# rPiMotors_v1_2.net
KiCad netlist of a schematic drawn in EAGLE
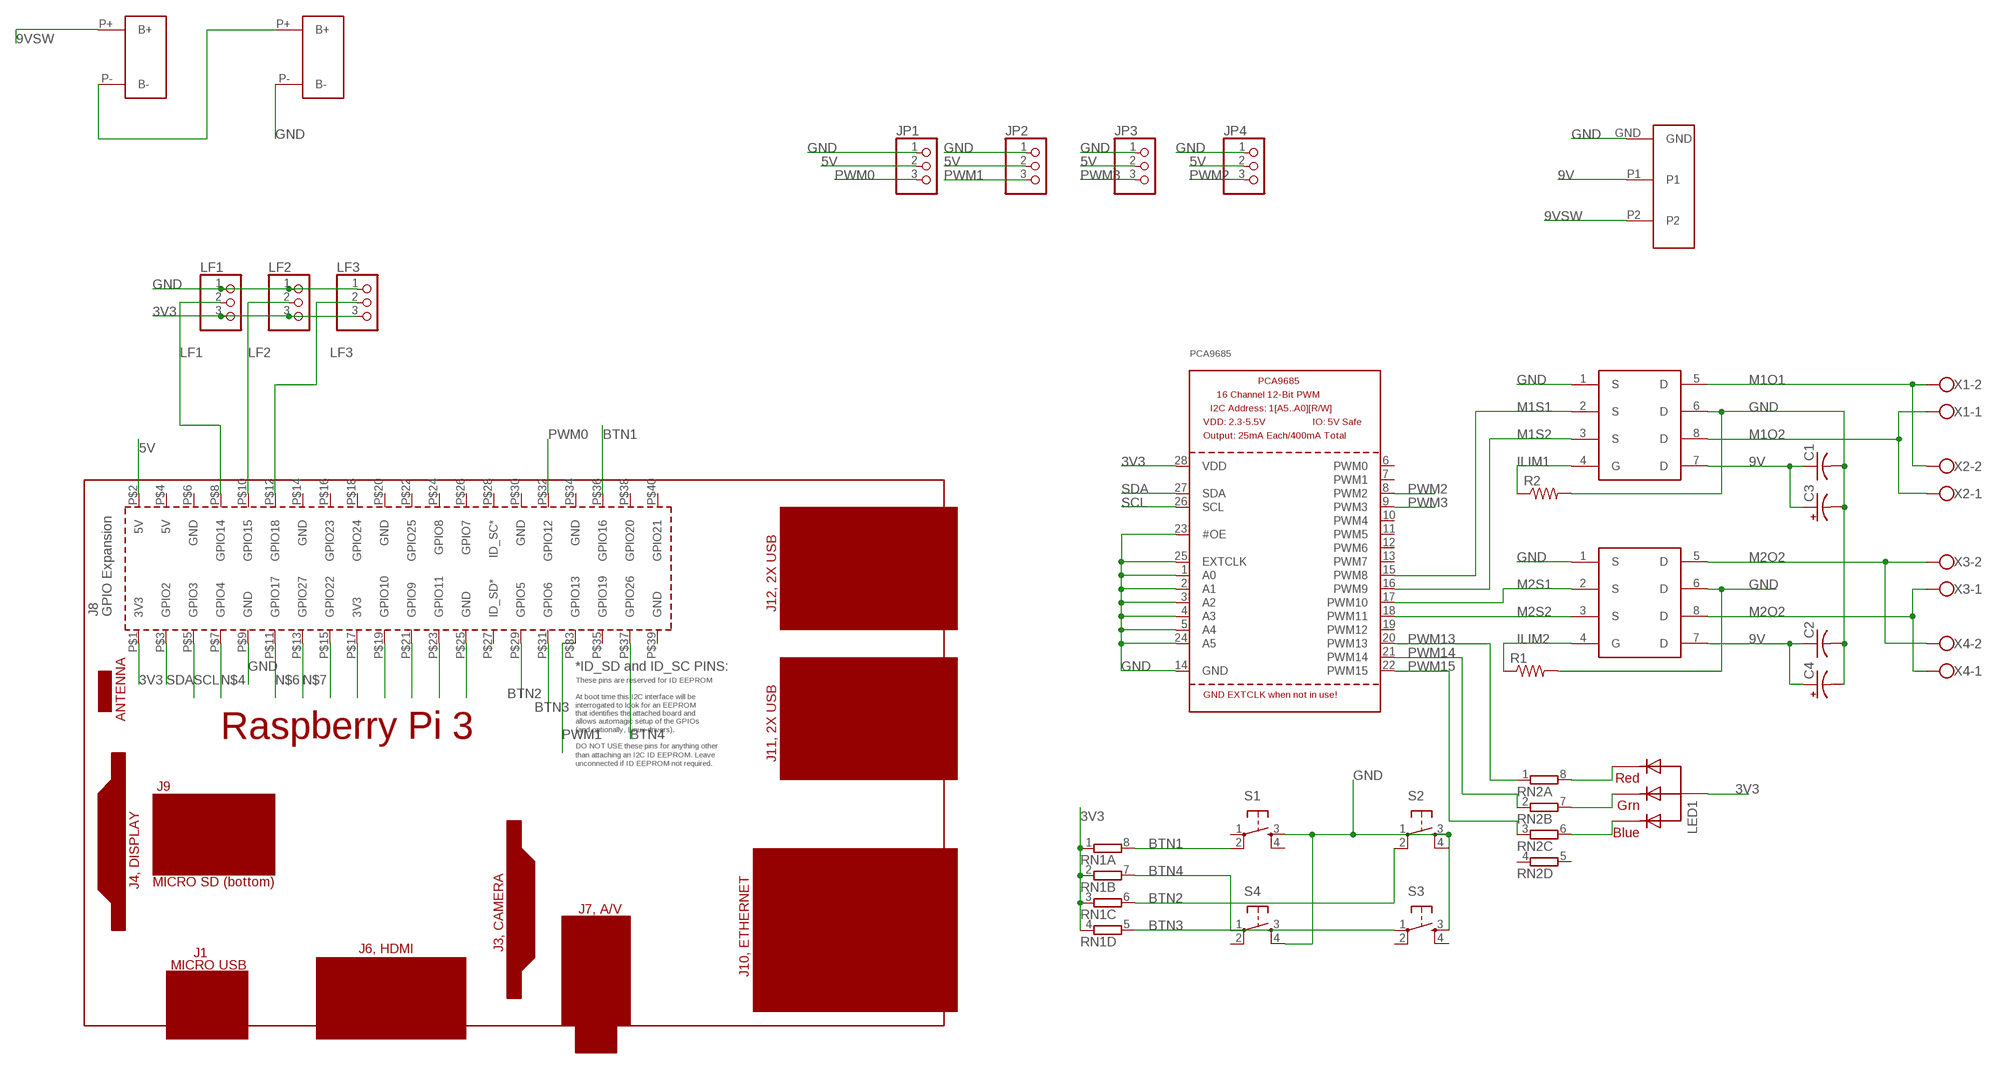
[diagram p0: schematic, sheet 1]

(export (version "E")
  (design (tool "Eeschema 10.0.6"))
  (components
    (comp (ref "C1")
      (value "C-USC0603")
      (footprint "eagle-import:C0603")
      (libsource (lib "eagle-import") (part "C-USC0603"))
    )
    (comp (ref "C2")
      (value "C-USC0603")
      (footprint "eagle-import:C0603")
      (libsource (lib "eagle-import") (part "C-USC0603"))
    )
    (comp (ref "C3")
      (value "CPOL-USD")
      (footprint "eagle-import:PANASONIC_D")
      (libsource (lib "eagle-import") (part "CPOL-USD"))
    )
    (comp (ref "C4")
      (value "CPOL-USD")
      (footprint "eagle-import:PANASONIC_D")
      (libsource (lib "eagle-import") (part "CPOL-USD"))
    )
    (comp (ref "JP1")
      (value "PINHD-1X3")
      (footprint "eagle-import:1X03")
      (libsource (lib "eagle-import") (part "PINHD-1X3"))
    )
    (comp (ref "JP2")
      (value "PINHD-1X3")
      (footprint "eagle-import:1X03")
      (libsource (lib "eagle-import") (part "PINHD-1X3"))
    )
    (comp (ref "JP3")
      (value "PINHD-1X3")
      (footprint "eagle-import:1X03")
      (libsource (lib "eagle-import") (part "PINHD-1X3"))
    )
    (comp (ref "JP4")
      (value "PINHD-1X3")
      (footprint "eagle-import:1X03")
      (libsource (lib "eagle-import") (part "PINHD-1X3"))
    )
    (comp (ref "LED1")
      (value "RGBLED_CA")
      (footprint "eagle-import:5MMRGB")
      (libsource (lib "eagle-import") (part "RGBLED_CA"))
    )
    (comp (ref "LF1")
      (value "PINHD-1X3")
      (footprint "eagle-import:1X03")
      (libsource (lib "eagle-import") (part "PINHD-1X3"))
    )
    (comp (ref "LF2")
      (value "PINHD-1X3")
      (footprint "eagle-import:1X03")
      (libsource (lib "eagle-import") (part "PINHD-1X3"))
    )
    (comp (ref "LF3")
      (value "PINHD-1X3")
      (footprint "eagle-import:1X03")
      (libsource (lib "eagle-import") (part "PINHD-1X3"))
    )
    (comp (ref "PCA9685")
      (value "PCA9685")
      (footprint "eagle-import:TSSOP28")
      (libsource (lib "eagle-import") (part "PCA9685"))
    )
    (comp (ref "PCB1")
      (value "RPI3")
      (footprint "eagle-import:RPI3")
      (libsource (lib "eagle-import") (part "RPI3"))
    )
    (comp (ref "R1")
      (value "R-US_R0603")
      (footprint "eagle-import:R0603")
      (libsource (lib "eagle-import") (part "R-US_R0603"))
    )
    (comp (ref "R2")
      (value "R-US_R0603")
      (footprint "eagle-import:R0603")
      (libsource (lib "eagle-import") (part "R-US_R0603"))
    )
    (comp (ref "RN1")
      (value "4R-N0603-ARV")
      (footprint "eagle-import:0603-ARV")
      (libsource (lib "eagle-import") (part "4R-N0603-ARV"))
    )
    (comp (ref "RN2")
      (value "4R-N0603-ARV")
      (footprint "eagle-import:0603-ARV")
      (libsource (lib "eagle-import") (part "4R-N0603-ARV"))
    )
    (comp (ref "S1")
      (value "TAC_SWITCHPTH")
      (footprint "eagle-import:TACTILE-PTH")
      (libsource (lib "eagle-import") (part "TAC_SWITCHPTH"))
    )
    (comp (ref "S2")
      (value "TAC_SWITCHPTH")
      (footprint "eagle-import:TACTILE-PTH")
      (libsource (lib "eagle-import") (part "TAC_SWITCHPTH"))
    )
    (comp (ref "S3")
      (value "TAC_SWITCHPTH")
      (footprint "eagle-import:TACTILE-PTH")
      (libsource (lib "eagle-import") (part "TAC_SWITCHPTH"))
    )
    (comp (ref "S4")
      (value "TAC_SWITCHPTH")
      (footprint "eagle-import:TACTILE-PTH")
      (libsource (lib "eagle-import") (part "TAC_SWITCHPTH"))
    )
    (comp (ref "U$1")
      (value "NDS8434")
      (footprint "eagle-import:SO08")
      (libsource (lib "eagle-import") (part "NDS8434"))
    )
    (comp (ref "U$2")
      (value "NDS8434")
      (footprint "eagle-import:SO08")
      (libsource (lib "eagle-import") (part "NDS8434"))
    )
    (comp (ref "U$3")
      (value "ROCKER")
      (footprint "eagle-import:ROCKER")
      (libsource (lib "eagle-import") (part "ROCKER"))
    )
    (comp (ref "U$4")
      (value "BATTERY")
      (footprint "eagle-import:BATTERY")
      (libsource (lib "eagle-import") (part "BATTERY"))
    )
    (comp (ref "U$5")
      (value "BATTERY")
      (footprint "eagle-import:BATTERY")
      (libsource (lib "eagle-import") (part "BATTERY"))
    )
    (comp (ref "X1")
      (value "SCREWCONNECTOR")
      (footprint "eagle-import:2PIN-SCREW-TERMINAL")
      (fields (field (name "MPN") "237-102"))
      (libsource (lib "eagle-import") (part "SCREWCONNECTOR"))
    )
    (comp (ref "X2")
      (value "SCREWCONNECTOR")
      (footprint "eagle-import:2PIN-SCREW-TERMINAL")
      (fields (field (name "MPN") "237-102"))
      (libsource (lib "eagle-import") (part "SCREWCONNECTOR"))
    )
    (comp (ref "X3")
      (value "SCREWCONNECTOR")
      (footprint "eagle-import:2PIN-SCREW-TERMINAL")
      (fields (field (name "MPN") "237-102"))
      (libsource (lib "eagle-import") (part "SCREWCONNECTOR"))
    )
    (comp (ref "X4")
      (value "SCREWCONNECTOR")
      (footprint "eagle-import:2PIN-SCREW-TERMINAL")
      (fields (field (name "MPN") "237-102"))
      (libsource (lib "eagle-import") (part "SCREWCONNECTOR"))
    )
  )
  (nets
    (net (code "1") (name "/3V3") (class "Default")
      (node (ref "LED1") (pin "2") (pinfunction "VCC_2") (pintype "bidirectional"))
      (node (ref "LF1") (pin "3") (pinfunction "3_3") (pintype "passive"))
      (node (ref "LF2") (pin "3") (pinfunction "3_3") (pintype "passive"))
      (node (ref "LF3") (pin "3") (pinfunction "3_3") (pintype "passive"))
      (node (ref "PCA9685") (pin "28") (pinfunction "VDD_28") (pintype "power_in"))
      (node (ref "PCB1") (pin "P$1") (pinfunction "3V3_P$1") (pintype "bidirectional"))
      (node (ref "RN1") (pin "1") (pinfunction "1_1") (pintype "passive"))
      (node (ref "RN1") (pin "2") (pinfunction "1_2") (pintype "passive"))
      (node (ref "RN1") (pin "3") (pinfunction "1_3") (pintype "passive"))
      (node (ref "RN1") (pin "4") (pinfunction "1_4") (pintype "passive"))
    )
    (net (code "2") (name "/5V") (class "Default")
      (node (ref "JP1") (pin "2") (pinfunction "2_2") (pintype "passive"))
      (node (ref "JP2") (pin "2") (pinfunction "2_2") (pintype "passive"))
      (node (ref "JP3") (pin "2") (pinfunction "2_2") (pintype "passive"))
      (node (ref "JP4") (pin "2") (pinfunction "2_2") (pintype "passive"))
      (node (ref "PCB1") (pin "P$2") (pinfunction "5V_P$2") (pintype "bidirectional"))
    )
    (net (code "3") (name "/9V") (class "Default")
      (node (ref "C1") (pin "1") (pinfunction "1_1") (pintype "passive"))
      (node (ref "C2") (pin "1") (pinfunction "1_1") (pintype "passive"))
      (node (ref "C3") (pin "+") (pinfunction "+_+") (pintype "passive"))
      (node (ref "C4") (pin "+") (pinfunction "+_+") (pintype "passive"))
      (node (ref "U$1") (pin "7") (pinfunction "D_7") (pintype "bidirectional"))
      (node (ref "U$2") (pin "7") (pinfunction "D_7") (pintype "bidirectional"))
      (node (ref "U$3") (pin "P1") (pinfunction "P1_P1") (pintype "bidirectional"))
    )
    (net (code "4") (name "/9VSW") (class "Default")
      (node (ref "U$3") (pin "P2") (pinfunction "P2_P2") (pintype "bidirectional"))
      (node (ref "U$4") (pin "P+") (pinfunction "B+_P+") (pintype "bidirectional"))
    )
    (net (code "5") (name "/BTN1") (class "Default")
      (node (ref "PCB1") (pin "P$36") (pinfunction "GPIO16_P$36") (pintype "bidirectional"))
      (node (ref "RN1") (pin "8") (pinfunction "2_8") (pintype "passive"))
      (node (ref "S1") (pin "2") (pinfunction "2_2") (pintype "passive"))
    )
    (net (code "6") (name "/BTN2") (class "Default")
      (node (ref "PCB1") (pin "P$29") (pinfunction "GPIO5_P$29") (pintype "bidirectional"))
      (node (ref "RN1") (pin "6") (pinfunction "2_6") (pintype "passive"))
      (node (ref "S2") (pin "2") (pinfunction "2_2") (pintype "passive"))
    )
    (net (code "7") (name "/BTN3") (class "Default")
      (node (ref "PCB1") (pin "P$31") (pinfunction "GPIO6_P$31") (pintype "bidirectional"))
      (node (ref "RN1") (pin "5") (pinfunction "2_5") (pintype "passive"))
      (node (ref "S3") (pin "1") (pinfunction "1_1") (pintype "passive"))
    )
    (net (code "8") (name "/BTN4") (class "Default")
      (node (ref "PCB1") (pin "P$37") (pinfunction "GPIO26_P$37") (pintype "bidirectional"))
      (node (ref "RN1") (pin "7") (pinfunction "2_7") (pintype "passive"))
      (node (ref "S4") (pin "1") (pinfunction "1_1") (pintype "passive"))
    )
    (net (code "9") (name "/GND") (class "Default")
      (node (ref "C1") (pin "2") (pinfunction "2_2") (pintype "passive"))
      (node (ref "C2") (pin "2") (pinfunction "2_2") (pintype "passive"))
      (node (ref "C3") (pin "-") (pinfunction "-_-") (pintype "passive"))
      (node (ref "C4") (pin "-") (pinfunction "-_-") (pintype "passive"))
      (node (ref "JP1") (pin "1") (pinfunction "1_1") (pintype "passive"))
      (node (ref "JP2") (pin "1") (pinfunction "1_1") (pintype "passive"))
      (node (ref "JP3") (pin "1") (pinfunction "1_1") (pintype "passive"))
      (node (ref "JP4") (pin "1") (pinfunction "1_1") (pintype "passive"))
      (node (ref "LF1") (pin "1") (pinfunction "1_1") (pintype "passive"))
      (node (ref "LF2") (pin "1") (pinfunction "1_1") (pintype "passive"))
      (node (ref "LF3") (pin "1") (pinfunction "1_1") (pintype "passive"))
      (node (ref "PCA9685") (pin "1") (pinfunction "A0_1") (pintype "bidirectional"))
      (node (ref "PCA9685") (pin "14") (pinfunction "GND_14") (pintype "power_in"))
      (node (ref "PCA9685") (pin "2") (pinfunction "A1_2") (pintype "bidirectional"))
      (node (ref "PCA9685") (pin "23") (pinfunction "#OE_23") (pintype "input"))
      (node (ref "PCA9685") (pin "24") (pinfunction "A5_24") (pintype "bidirectional"))
      (node (ref "PCA9685") (pin "25") (pinfunction "EXTCLK_25") (pintype "input"))
      (node (ref "PCA9685") (pin "3") (pinfunction "A2_3") (pintype "bidirectional"))
      (node (ref "PCA9685") (pin "4") (pinfunction "A3_4") (pintype "bidirectional"))
      (node (ref "PCA9685") (pin "5") (pinfunction "A4_5") (pintype "bidirectional"))
      (node (ref "PCB1") (pin "P$9") (pinfunction "GND_P$9") (pintype "bidirectional"))
      (node (ref "R1") (pin "2") (pinfunction "2_2") (pintype "passive"))
      (node (ref "R2") (pin "2") (pinfunction "2_2") (pintype "passive"))
      (node (ref "S1") (pin "3") (pinfunction "3_3") (pintype "passive"))
      (node (ref "S2") (pin "3") (pinfunction "3_3") (pintype "passive"))
      (node (ref "S3") (pin "3") (pinfunction "3_3") (pintype "passive"))
      (node (ref "S4") (pin "4") (pinfunction "4_4") (pintype "passive"))
      (node (ref "U$1") (pin "1") (pinfunction "S_1") (pintype "bidirectional"))
      (node (ref "U$1") (pin "6") (pinfunction "D_6") (pintype "bidirectional"))
      (node (ref "U$2") (pin "1") (pinfunction "S_1") (pintype "bidirectional"))
      (node (ref "U$2") (pin "6") (pinfunction "D_6") (pintype "bidirectional"))
      (node (ref "U$3") (pin "GND") (pinfunction "GND_GND") (pintype "bidirectional"))
      (node (ref "U$5") (pin "P-") (pinfunction "B-_P-") (pintype "bidirectional"))
    )
    (net (code "10") (name "/ILIM1") (class "Default")
      (node (ref "R2") (pin "1") (pinfunction "1_1") (pintype "passive"))
      (node (ref "U$1") (pin "4") (pinfunction "G_4") (pintype "bidirectional"))
    )
    (net (code "11") (name "/ILIM2") (class "Default")
      (node (ref "R1") (pin "1") (pinfunction "1_1") (pintype "passive"))
      (node (ref "U$2") (pin "4") (pinfunction "G_4") (pintype "bidirectional"))
    )
    (net (code "12") (name "/LF1") (class "Default")
      (node (ref "LF1") (pin "2") (pinfunction "2_2") (pintype "passive"))
      (node (ref "PCB1") (pin "P$8") (pinfunction "GPIO14_P$8") (pintype "bidirectional"))
    )
    (net (code "13") (name "/LF2") (class "Default")
      (node (ref "LF2") (pin "2") (pinfunction "2_2") (pintype "passive"))
      (node (ref "PCB1") (pin "P$10") (pinfunction "GPIO15_P$10") (pintype "bidirectional"))
    )
    (net (code "14") (name "/LF3") (class "Default")
      (node (ref "LF3") (pin "2") (pinfunction "2_2") (pintype "passive"))
      (node (ref "PCB1") (pin "P$12") (pinfunction "GPIO18_P$12") (pintype "bidirectional"))
    )
    (net (code "15") (name "/M1O1") (class "Default")
      (node (ref "U$1") (pin "5") (pinfunction "D_5") (pintype "bidirectional"))
      (node (ref "X1") (pin "2") (pinfunction "KL_2") (pintype "passive"))
      (node (ref "X2") (pin "2") (pinfunction "KL_2") (pintype "passive"))
    )
    (net (code "16") (name "/M1O2") (class "Default")
      (node (ref "U$1") (pin "8") (pinfunction "D_8") (pintype "bidirectional"))
      (node (ref "X1") (pin "1") (pinfunction "KL_1") (pintype "passive"))
      (node (ref "X2") (pin "1") (pinfunction "KL_1") (pintype "passive"))
    )
    (net (code "17") (name "/M1S1") (class "Default")
      (node (ref "PCA9685") (pin "15") (pinfunction "PWM8_15") (pintype "output"))
      (node (ref "U$1") (pin "2") (pinfunction "S_2") (pintype "bidirectional"))
    )
    (net (code "18") (name "/M1S2") (class "Default")
      (node (ref "PCA9685") (pin "16") (pinfunction "PWM9_16") (pintype "output"))
      (node (ref "U$1") (pin "3") (pinfunction "S_3") (pintype "bidirectional"))
    )
    (net (code "19") (name "/M2O2") (class "Default")
      (node (ref "U$2") (pin "5") (pinfunction "D_5") (pintype "bidirectional"))
      (node (ref "U$2") (pin "8") (pinfunction "D_8") (pintype "bidirectional"))
      (node (ref "X3") (pin "1") (pinfunction "KL_1") (pintype "passive"))
      (node (ref "X3") (pin "2") (pinfunction "KL_2") (pintype "passive"))
      (node (ref "X4") (pin "1") (pinfunction "KL_1") (pintype "passive"))
      (node (ref "X4") (pin "2") (pinfunction "KL_2") (pintype "passive"))
    )
    (net (code "20") (name "/M2S1") (class "Default")
      (node (ref "PCA9685") (pin "17") (pinfunction "PWM10_17") (pintype "output"))
      (node (ref "U$2") (pin "2") (pinfunction "S_2") (pintype "bidirectional"))
    )
    (net (code "21") (name "/M2S2") (class "Default")
      (node (ref "PCA9685") (pin "18") (pinfunction "PWM11_18") (pintype "output"))
      (node (ref "U$2") (pin "3") (pinfunction "S_3") (pintype "bidirectional"))
    )
    (net (code "22") (name "/N$4") (class "Default")
      (node (ref "PCB1") (pin "P$7") (pinfunction "GPIO4_P$7") (pintype "bidirectional"))
    )
    (net (code "23") (name "/N$6") (class "Default")
      (node (ref "PCB1") (pin "P$11") (pinfunction "GPIO17_P$11") (pintype "bidirectional"))
    )
    (net (code "24") (name "/N$7") (class "Default")
      (node (ref "PCB1") (pin "P$13") (pinfunction "GPIO27_P$13") (pintype "bidirectional"))
    )
    (net (code "25") (name "/PWM0") (class "Default")
      (node (ref "JP1") (pin "3") (pinfunction "3_3") (pintype "passive"))
      (node (ref "PCB1") (pin "P$32") (pinfunction "GPIO12_P$32") (pintype "bidirectional"))
    )
    (net (code "26") (name "/PWM1") (class "Default")
      (node (ref "JP2") (pin "3") (pinfunction "3_3") (pintype "passive"))
      (node (ref "PCB1") (pin "P$33") (pinfunction "GPIO13_P$33") (pintype "bidirectional"))
    )
    (net (code "27") (name "/PWM2") (class "Default")
      (node (ref "JP4") (pin "3") (pinfunction "3_3") (pintype "passive"))
      (node (ref "PCA9685") (pin "8") (pinfunction "PWM2_8") (pintype "output"))
    )
    (net (code "28") (name "/PWM3") (class "Default")
      (node (ref "JP3") (pin "3") (pinfunction "3_3") (pintype "passive"))
      (node (ref "PCA9685") (pin "9") (pinfunction "PWM3_9") (pintype "output"))
    )
    (net (code "29") (name "/PWM13") (class "Default")
      (node (ref "PCA9685") (pin "20") (pinfunction "PWM13_20") (pintype "output"))
      (node (ref "RN2") (pin "1") (pinfunction "1_1") (pintype "passive"))
    )
    (net (code "30") (name "/PWM14") (class "Default")
      (node (ref "PCA9685") (pin "21") (pinfunction "PWM14_21") (pintype "output"))
      (node (ref "RN2") (pin "2") (pinfunction "1_2") (pintype "passive"))
    )
    (net (code "31") (name "/PWM15") (class "Default")
      (node (ref "PCA9685") (pin "22") (pinfunction "PWM15_22") (pintype "output"))
      (node (ref "RN2") (pin "3") (pinfunction "1_3") (pintype "passive"))
    )
    (net (code "32") (name "/SCL") (class "Default")
      (node (ref "PCA9685") (pin "26") (pinfunction "SCL_26") (pintype "bidirectional"))
      (node (ref "PCB1") (pin "P$5") (pinfunction "GPIO3_P$5") (pintype "bidirectional"))
    )
    (net (code "33") (name "/SDA") (class "Default")
      (node (ref "PCA9685") (pin "27") (pinfunction "SDA_27") (pintype "bidirectional"))
      (node (ref "PCB1") (pin "P$3") (pinfunction "GPIO2_P$3") (pintype "bidirectional"))
    )
    (net (code "34") (name "Net-(LED1-BLUE)") (class "Default")
      (node (ref "LED1") (pin "1") (pinfunction "BLUE_1") (pintype "bidirectional"))
      (node (ref "RN2") (pin "6") (pinfunction "2_6") (pintype "passive"))
    )
    (net (code "35") (name "Net-(LED1-GREEN)") (class "Default")
      (node (ref "LED1") (pin "3") (pinfunction "GREEN_3") (pintype "bidirectional"))
      (node (ref "RN2") (pin "7") (pinfunction "2_7") (pintype "passive"))
    )
    (net (code "36") (name "Net-(LED1-RED)") (class "Default")
      (node (ref "LED1") (pin "4") (pinfunction "RED_4") (pintype "bidirectional"))
      (node (ref "RN2") (pin "8") (pinfunction "2_8") (pintype "passive"))
    )
    (net (code "37") (name "Net-(U$4-B-)") (class "Default")
      (node (ref "U$4") (pin "P-") (pinfunction "B-_P-") (pintype "bidirectional"))
      (node (ref "U$5") (pin "P+") (pinfunction "B+_P+") (pintype "bidirectional"))
    )
    (net (code "38") (name "unconnected-(PCA9685-PWM0-Pad6)") (class "Default")
      (node (ref "PCA9685") (pin "6") (pinfunction "PWM0_6") (pintype "output"))
    )
    (net (code "39") (name "unconnected-(PCA9685-PWM1-Pad7)") (class "Default")
      (node (ref "PCA9685") (pin "7") (pinfunction "PWM1_7") (pintype "output"))
    )
    (net (code "40") (name "unconnected-(PCA9685-PWM4-Pad10)") (class "Default")
      (node (ref "PCA9685") (pin "10") (pinfunction "PWM4_10") (pintype "output"))
    )
    (net (code "41") (name "unconnected-(PCA9685-PWM5-Pad11)") (class "Default")
      (node (ref "PCA9685") (pin "11") (pinfunction "PWM5_11") (pintype "output"))
    )
    (net (code "42") (name "unconnected-(PCA9685-PWM6-Pad12)") (class "Default")
      (node (ref "PCA9685") (pin "12") (pinfunction "PWM6_12") (pintype "output"))
    )
    (net (code "43") (name "unconnected-(PCA9685-PWM7-Pad13)") (class "Default")
      (node (ref "PCA9685") (pin "13") (pinfunction "PWM7_13") (pintype "output"))
    )
    (net (code "44") (name "unconnected-(PCA9685-PWM12-Pad19)") (class "Default")
      (node (ref "PCA9685") (pin "19") (pinfunction "PWM12_19") (pintype "output"))
    )
    (net (code "45") (name "unconnected-(PCB1-3V3-PadP$17)") (class "Default")
      (node (ref "PCB1") (pin "P$17") (pinfunction "3V3_P$17") (pintype "bidirectional"))
    )
    (net (code "46") (name "unconnected-(PCB1-5V-PadP$4)") (class "Default")
      (node (ref "PCB1") (pin "P$4") (pinfunction "5V_P$4") (pintype "bidirectional"))
    )
    (net (code "47") (name "unconnected-(PCB1-GND-PadP$6)") (class "Default")
      (node (ref "PCB1") (pin "P$6") (pinfunction "GND_P$6") (pintype "bidirectional"))
    )
    (net (code "48") (name "unconnected-(PCB1-GND-PadP$14)") (class "Default")
      (node (ref "PCB1") (pin "P$14") (pinfunction "GND_P$14") (pintype "bidirectional"))
    )
    (net (code "49") (name "unconnected-(PCB1-GND-PadP$20)") (class "Default")
      (node (ref "PCB1") (pin "P$20") (pinfunction "GND_P$20") (pintype "bidirectional"))
    )
    (net (code "50") (name "unconnected-(PCB1-GND-PadP$25)") (class "Default")
      (node (ref "PCB1") (pin "P$25") (pinfunction "GND_P$25") (pintype "bidirectional"))
    )
    (net (code "51") (name "unconnected-(PCB1-GND-PadP$30)") (class "Default")
      (node (ref "PCB1") (pin "P$30") (pinfunction "GND_P$30") (pintype "bidirectional"))
    )
    (net (code "52") (name "unconnected-(PCB1-GND-PadP$34)") (class "Default")
      (node (ref "PCB1") (pin "P$34") (pinfunction "GND_P$34") (pintype "bidirectional"))
    )
    (net (code "53") (name "unconnected-(PCB1-GND-PadP$39)") (class "Default")
      (node (ref "PCB1") (pin "P$39") (pinfunction "GND_P$39") (pintype "bidirectional"))
    )
    (net (code "54") (name "unconnected-(PCB1-GPIO7-PadP$26)") (class "Default")
      (node (ref "PCB1") (pin "P$26") (pinfunction "GPIO7_P$26") (pintype "bidirectional"))
    )
    (net (code "55") (name "unconnected-(PCB1-GPIO8-PadP$24)") (class "Default")
      (node (ref "PCB1") (pin "P$24") (pinfunction "GPIO8_P$24") (pintype "bidirectional"))
    )
    (net (code "56") (name "unconnected-(PCB1-GPIO9-PadP$21)") (class "Default")
      (node (ref "PCB1") (pin "P$21") (pinfunction "GPIO9_P$21") (pintype "bidirectional"))
    )
    (net (code "57") (name "unconnected-(PCB1-GPIO10-PadP$19)") (class "Default")
      (node (ref "PCB1") (pin "P$19") (pinfunction "GPIO10_P$19") (pintype "bidirectional"))
    )
    (net (code "58") (name "unconnected-(PCB1-GPIO11-PadP$23)") (class "Default")
      (node (ref "PCB1") (pin "P$23") (pinfunction "GPIO11_P$23") (pintype "bidirectional"))
    )
    (net (code "59") (name "unconnected-(PCB1-GPIO19-PadP$35)") (class "Default")
      (node (ref "PCB1") (pin "P$35") (pinfunction "GPIO19_P$35") (pintype "bidirectional"))
    )
    (net (code "60") (name "unconnected-(PCB1-GPIO20-PadP$38)") (class "Default")
      (node (ref "PCB1") (pin "P$38") (pinfunction "GPIO20_P$38") (pintype "bidirectional"))
    )
    (net (code "61") (name "unconnected-(PCB1-GPIO21-PadP$40)") (class "Default")
      (node (ref "PCB1") (pin "P$40") (pinfunction "GPIO21_P$40") (pintype "bidirectional"))
    )
    (net (code "62") (name "unconnected-(PCB1-GPIO22-PadP$15)") (class "Default")
      (node (ref "PCB1") (pin "P$15") (pinfunction "GPIO22_P$15") (pintype "bidirectional"))
    )
    (net (code "63") (name "unconnected-(PCB1-GPIO23-PadP$16)") (class "Default")
      (node (ref "PCB1") (pin "P$16") (pinfunction "GPIO23_P$16") (pintype "bidirectional"))
    )
    (net (code "64") (name "unconnected-(PCB1-GPIO24-PadP$18)") (class "Default")
      (node (ref "PCB1") (pin "P$18") (pinfunction "GPIO24_P$18") (pintype "bidirectional"))
    )
    (net (code "65") (name "unconnected-(PCB1-GPIO25-PadP$22)") (class "Default")
      (node (ref "PCB1") (pin "P$22") (pinfunction "GPIO25_P$22") (pintype "bidirectional"))
    )
    (net (code "66") (name "unconnected-(PCB1-ID_SC*-PadP$28)") (class "Default")
      (node (ref "PCB1") (pin "P$28") (pinfunction "ID_SC*_P$28") (pintype "bidirectional"))
    )
    (net (code "67") (name "unconnected-(PCB1-ID_SD*-PadP$27)") (class "Default")
      (node (ref "PCB1") (pin "P$27") (pinfunction "ID_SD*_P$27") (pintype "bidirectional"))
    )
    (net (code "68") (name "unconnected-(RN2D-1-Pad4)") (class "Default")
      (node (ref "RN2") (pin "4") (pinfunction "1_4") (pintype "passive"))
    )
    (net (code "69") (name "unconnected-(RN2D-2-Pad5)") (class "Default")
      (node (ref "RN2") (pin "5") (pinfunction "2_5") (pintype "passive"))
    )
    (net (code "70") (name "unconnected-(S1-Pad1)") (class "Default")
      (node (ref "S1") (pin "1") (pinfunction "1_1") (pintype "passive"))
    )
    (net (code "71") (name "unconnected-(S1-Pad4)") (class "Default")
      (node (ref "S1") (pin "4") (pinfunction "4_4") (pintype "passive"))
    )
    (net (code "72") (name "unconnected-(S2-Pad1)") (class "Default")
      (node (ref "S2") (pin "1") (pinfunction "1_1") (pintype "passive"))
    )
    (net (code "73") (name "unconnected-(S2-Pad4)") (class "Default")
      (node (ref "S2") (pin "4") (pinfunction "4_4") (pintype "passive"))
    )
    (net (code "74") (name "unconnected-(S3-Pad2)") (class "Default")
      (node (ref "S3") (pin "2") (pinfunction "2_2") (pintype "passive"))
    )
    (net (code "75") (name "unconnected-(S3-Pad4)") (class "Default")
      (node (ref "S3") (pin "4") (pinfunction "4_4") (pintype "passive"))
    )
    (net (code "76") (name "unconnected-(S4-Pad2)") (class "Default")
      (node (ref "S4") (pin "2") (pinfunction "2_2") (pintype "passive"))
    )
    (net (code "77") (name "unconnected-(S4-Pad3)") (class "Default")
      (node (ref "S4") (pin "3") (pinfunction "3_3") (pintype "passive"))
    )
  )
)
